# JM24023-Y009-A-V1_0.net
KiCad netlist of a schematic drawn in Altium Designer
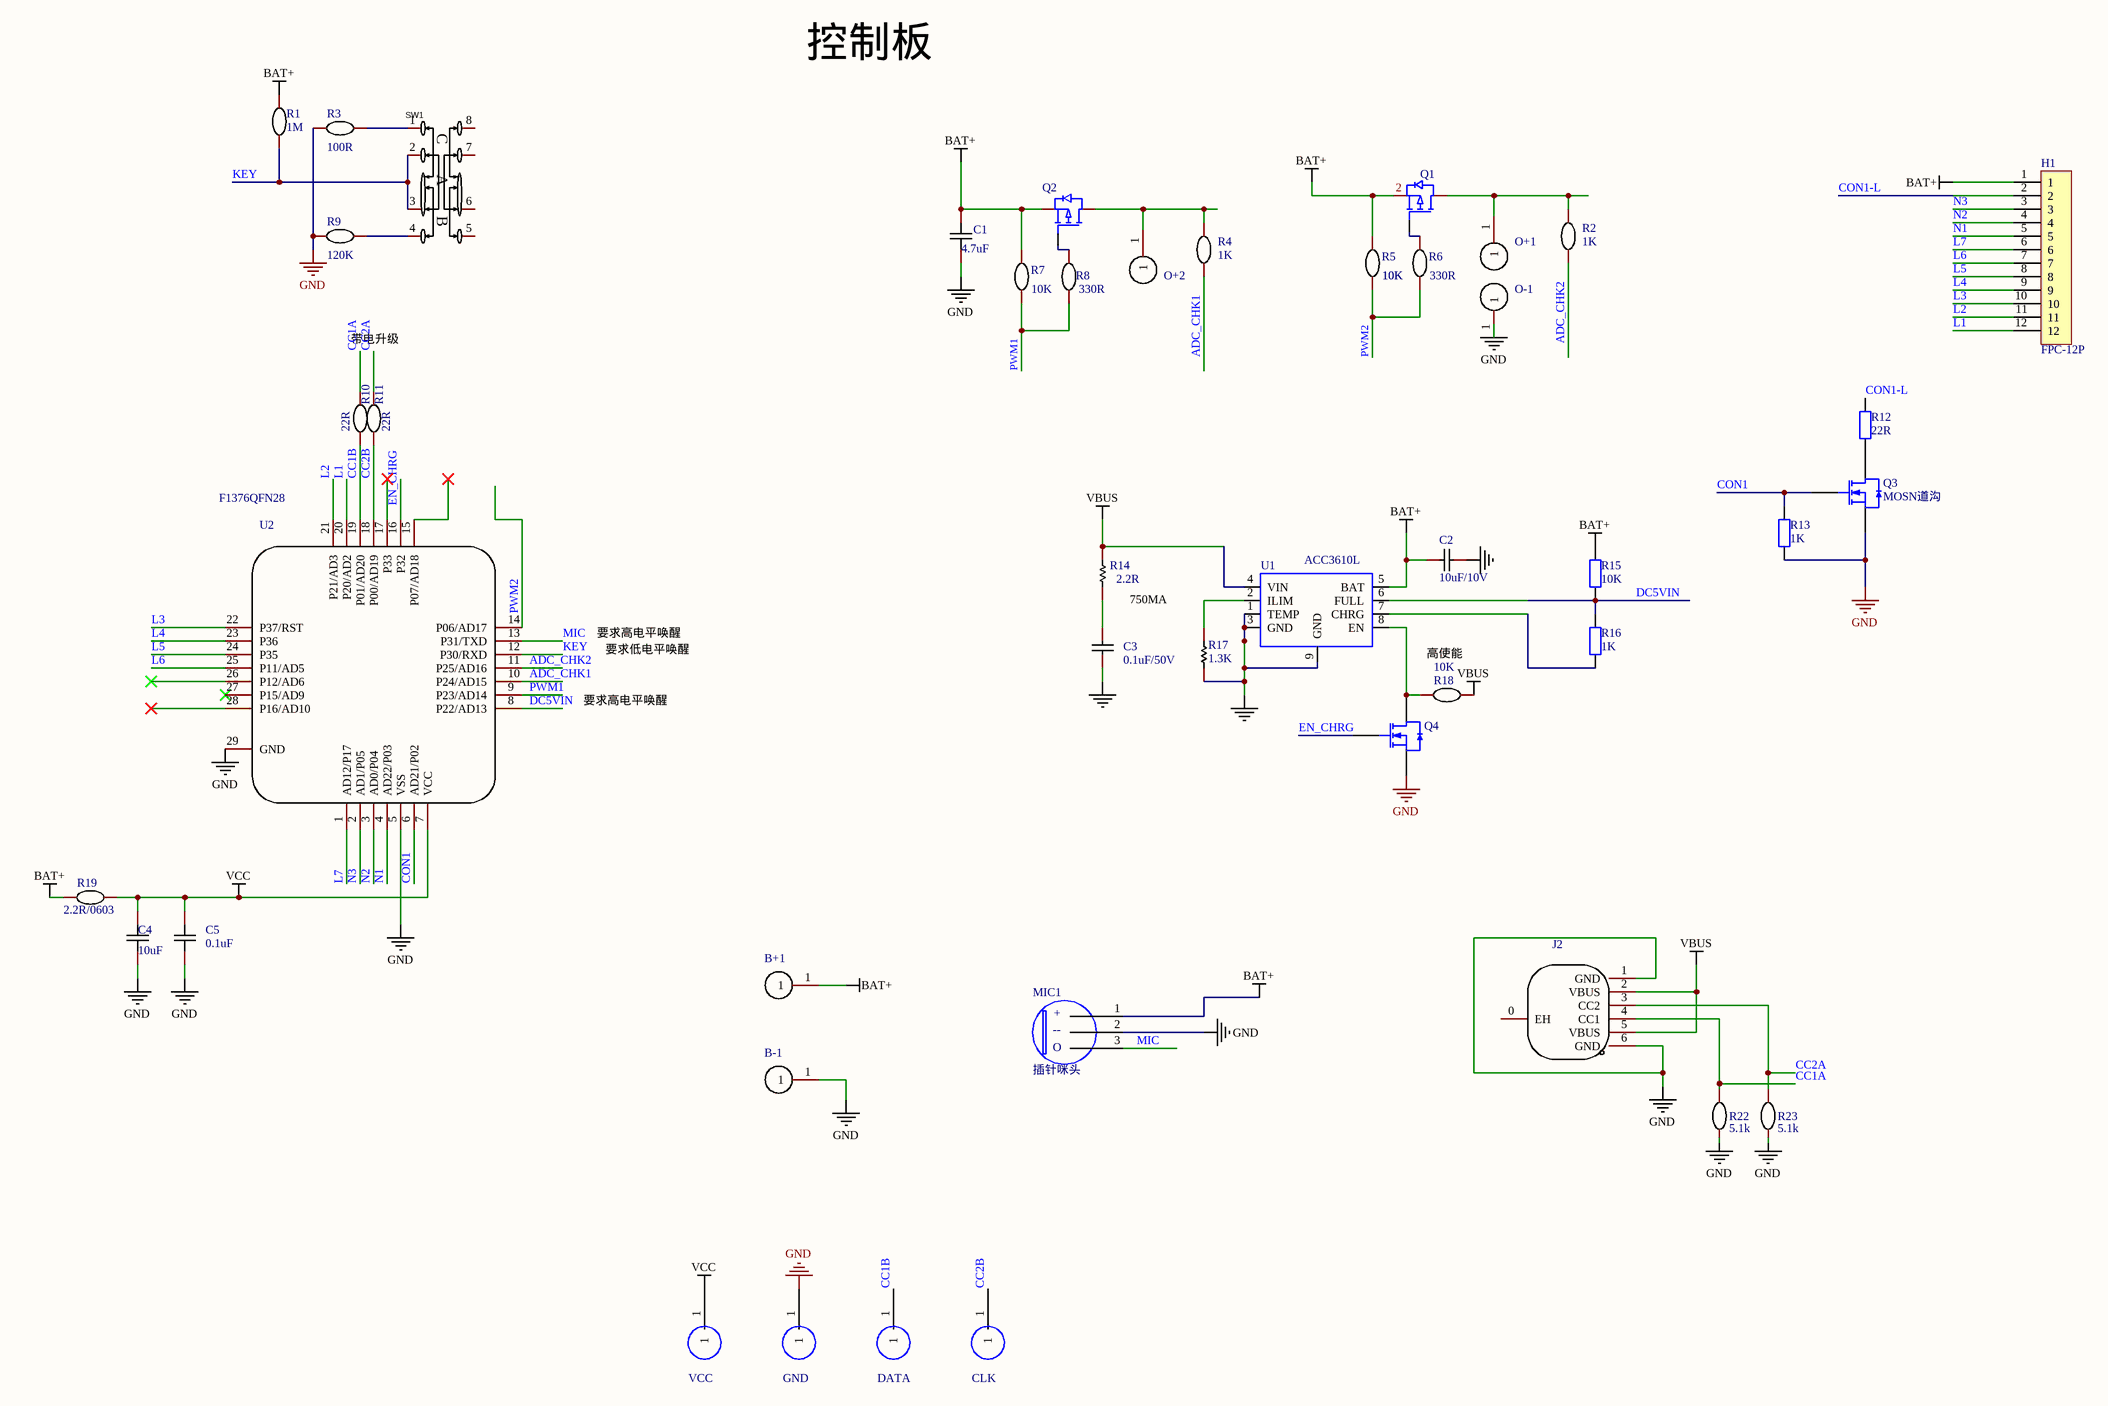
[diagram p0: JM24023-Y009-A-V1.0.schdoc]

(export (version "E")
  (design (tool "Eeschema 10.0.6"))
  (components
    (comp (ref "B+1")
      (value "电池正")
      (footprint "TP1.5")
      (fields (field (name "MANUFACTURER") "XFCN(兴飞)") (field (name "MANUFACTURER PART") "PZ254V-11-01P"))
      (libsource (lib "altium-import") (part "root_2_电池正_"))
    )
    (comp (ref "B-1")
      (value "电池负")
      (footprint "TP1.5")
      (fields (field (name "MANUFACTURER") "XFCN(兴飞)") (field (name "MANUFACTURER PART") "PZ254V-11-01P"))
      (libsource (lib "altium-import") (part "root_2_电池负_"))
    )
    (comp (ref "C1")
      (value "4.7uF10V")
      (footprint "C0402S")
      (fields (field (name "DEVICE") "4.7uF"))
      (libsource (lib "altium-import") (part "root_1_4.7uF10V_"))
    )
    (comp (ref "C2")
      (value "10uF/10V")
      (footprint "C0402S")
      (libsource (lib "altium-import") (part "root_2_10uF/10V_"))
    )
    (comp (ref "C3")
      (value "0.1uF/50V")
      (footprint "C0402S")
      (fields (field (name "NAME") "0.1uF/50V"))
      (libsource (lib "altium-import") (part "root_1_0.1uF/50V_"))
    )
    (comp (ref "C4")
      (value "10uF")
      (footprint "C0402S")
      (fields (field (name "NAME") "10uF"))
      (libsource (lib "altium-import") (part "root_3_mirrored_10uF_"))
    )
    (comp (ref "C5")
      (value "0.1uF")
      (footprint "C0402S")
      (fields (field (name "NAME") "0.1uF"))
      (libsource (lib "altium-import") (part "root_3_mirrored_0.1uF_"))
    )
    (comp (ref "CLK") (value "PAD-烧入测试") (footprint "TP1.5") (libsource (lib "JM原理图库") (part "PAD-烧入测试")))
    (comp (ref "DATA") (value "PAD-烧入测试") (footprint "TP1.5") (libsource (lib "JM原理图库") (part "PAD-烧入测试")))
    (comp (ref "GND") (value "PAD-烧入测试") (footprint "TP1.5") (libsource (lib "JM原理图库") (part "PAD-烧入测试")))
    (comp (ref "H1")
      (value "FPC-12P")
      (footprint "CONN-SMD_12P-P0.50_L3.1-W8.0")
      (libsource (lib "JM原理图库") (part "FPC-12P"))
    )
    (comp (ref "J2")
      (value "TYPE-C 6P(073)-6.5MM")
      (footprint "USB_TYPEC_6L8 -2.0立贴")
      (fields
        (field (name "MANUFACTURER") "SHOU HAN(首韩)")
        (field (name "MANUFACTURER PART") "TYPE-C 6P(073)")
      )
      (libsource (lib "altium-import") (part "root_2_TYPE-C 6P(073)-6.5MM_"))
    )
    (comp (ref "MIC1") (value "插针咪头") (footprint "三针咪/一芯微") (libsource (lib "JM原理图库") (part "3Lin咪头")))
    (comp (ref "O+1")
      (value "加热丝输出")
      (footprint "TP1.5")
      (fields (field (name "MANUFACTURER") "XFCN(兴飞)") (field (name "MANUFACTURER PART") "PZ254V-11-01P"))
      (libsource (lib "altium-import") (part "root_3_加热丝输出_"))
    )
    (comp (ref "O+2")
      (value "加热丝输出")
      (footprint "TP1.5")
      (fields (field (name "MANUFACTURER") "XFCN(兴飞)") (field (name "MANUFACTURER PART") "PZ254V-11-01P"))
      (libsource (lib "altium-import") (part "root_3_加热丝输出_"))
    )
    (comp (ref "O-1")
      (value "加热丝输出")
      (footprint "TP1.5")
      (fields (field (name "MANUFACTURER") "XFCN(兴飞)") (field (name "MANUFACTURER PART") "PZ254V-11-01P"))
      (libsource (lib "altium-import") (part "root_1_加热丝输出_"))
    )
    (comp (ref "Q1")
      (value "P沟场效应管")
      (footprint "SOT-23-3_L2.9-W1.6-P1.90-LS2.8-BR")
      (description "P-Channel Switch with Low RDS(on),SMD,VDS=-20V VGS=±12V ID-0.66A RDS(on)=7Ω")
      (libsource (lib "") (part "PMOS_1"))
    )
    (comp (ref "Q2")
      (value "P沟场效应管")
      (footprint "SOT-23-3_L2.9-W1.6-P1.90-LS2.8-BR")
      (description "P-Channel Switch with Low RDS(on),SMD,VDS=-20V VGS=±12V ID-0.66A RDS(on)=7Ω")
      (libsource (lib "JM原理图库") (part "PMOS"))
    )
    (comp (ref "Q3")
      (value "MOSN道沟")
      (footprint "SOT-523-3_L1.7-W0.8-P1.00-LS1.5-BR")
      (description "MOS(场效应管)")
      (libsource (lib "JM原理图库") (part "MOSN道沟"))
    )
    (comp (ref "Q4")
      (value "~")
      (footprint "SOT-523-3_L1.7-W0.8-P1.00-LS1.5-BR")
      (description "MOS(场效应管)")
      (libsource (lib "JM原理图库") (part "MOSN道沟"))
    )
    (comp (ref "R1")
      (value "1M")
      (footprint "R0402S")
      (fields (field (name "NAME") "1M"))
      (libsource (lib "altium-import") (part "root_1_47K_"))
    )
    (comp (ref "R2")
      (value "1K")
      (footprint "R0402S")
      (fields (field (name "NAME") "1K"))
      (libsource (lib "altium-import") (part "root_3_1K_"))
    )
    (comp (ref "R3")
      (value "100R")
      (footprint "R0402S")
      (libsource (lib "altium-import") (part "root_2_47K_"))
    )
    (comp (ref "R4")
      (value "1K")
      (footprint "R0402S")
      (fields (field (name "NAME") "1K"))
      (libsource (lib "altium-import") (part "root_3_1K_"))
    )
    (comp (ref "R5")
      (value "10K")
      (footprint "R0402S")
      (fields (field (name "NAME") "10K") (field (name "DEVICE") "10K"))
      (libsource (lib "altium-import") (part "root_1_10K_"))
    )
    (comp (ref "R6")
      (value "330R")
      (footprint "R0402S")
      (fields (field (name "NAME") "330R"))
      (libsource (lib "altium-import") (part "root_1_330R_"))
    )
    (comp (ref "R7")
      (value "10K")
      (footprint "R0402S")
      (fields (field (name "DEVICE") "10K"))
      (libsource (lib "altium-import") (part "root_1_10K_"))
    )
    (comp (ref "R8")
      (value "330R")
      (footprint "R0402S")
      (fields (field (name "DEVICE") "330R"))
      (libsource (lib "altium-import") (part "root_1_330R_"))
    )
    (comp (ref "R9")
      (value "120K")
      (footprint "R0402S")
      (libsource (lib "altium-import") (part "root_2_47K_"))
    )
    (comp (ref "R10")
      (value "22R")
      (footprint "R0402S")
      (libsource (lib "altium-import") (part "root_3_22R_"))
    )
    (comp (ref "R11")
      (value "22R")
      (footprint "R0402S")
      (libsource (lib "altium-import") (part "root_3_22R_"))
    )
    (comp (ref "R12")
      (value "22R")
      (footprint "R0402S")
      (description "贴片电阻")
      (libsource (lib "JM原理图库") (part "RES 1%"))
    )
    (comp (ref "R13")
      (value "1K")
      (footprint "R0402S")
      (description "贴片电阻")
      (libsource (lib "JM原理图库") (part "RES 1%"))
    )
    (comp (ref "R14")
      (value "2.2R")
      (footprint "R0402S")
      (fields (field (name "NAME") "2.2R"))
      (libsource (lib "altium-import") (part "root_1_2R2/0402_"))
    )
    (comp (ref "R15")
      (value "10K")
      (footprint "R0402S")
      (description "贴片电阻")
      (libsource (lib "") (part "RES 1%_1"))
    )
    (comp (ref "R16")
      (value "1K")
      (footprint "R0402S")
      (description "贴片电阻")
      (libsource (lib "") (part "RES 1%_1"))
    )
    (comp (ref "R17")
      (value "1.3K")
      (footprint "R0402S")
      (fields (field (name "DEVICE") "1.3K"))
      (libsource (lib "altium-import") (part "root_3_1.3K_"))
    )
    (comp (ref "R18")
      (value "10k")
      (footprint "R0402S")
      (description "电阻类型:厚膜电阻;阻值:10kΩ;精度:±1%;功率:62.5mW;最大工作电压:50V;温度系数:±100ppm/℃;")
      (fields
        (field (name "SYMBOL") "10K")
        (field (name "MANUFACTURER") "YAGEO(国巨)")
        (field (name "MANUFACTURER PART") "RC0402FR-0710KL")
      )
      (libsource (lib "altium-import") (part "root_2_RC0402FR-0710KL_"))
    )
    (comp (ref "R19")
      (value "2.2R/0603")
      (footprint "R0603S")
      (libsource (lib "altium-import") (part "root_0_2.2R/0805_"))
    )
    (comp (ref "R22")
      (value "5.1k")
      (footprint "R0402S")
      (fields (field (name "NAME") "5.1k"))
      (libsource (lib "altium-import") (part "root_1_5.1k_"))
    )
    (comp (ref "R23")
      (value "5.1k")
      (footprint "R0402S")
      (fields (field (name "NAME") "5.1k"))
      (libsource (lib "altium-import") (part "root_1_5.1k_"))
    )
    (comp (ref "SW1")
      (value "SW1")
      (footprint "SW-SMD_8P-L9.9-W3.5-P2.00")
      (fields (field (name "MANUFACTURER") "Yuandi(元迪)") (field (name "MANUFACTURER PART") "TA-3537S-A1"))
      (libsource (lib "JM原理图库") (part "8脚3档拨动开关"))
    )
    (comp (ref "U1")
      (value "ACC3610L")
      (footprint "DFN-8-2X2-P0.50-TL-EP1.6")
      (description "36V 集成 OVP 保护 1.0A 锂电池线性充电芯片")
      (libsource (lib "JM原理图库") (part "SA4356"))
    )
    (comp (ref "U2")
      (value "F1376QFN28")
      (footprint "QFN-28_L4.0-W4.0-P0.40-BL-EP2.6")
      (libsource (lib "altium-import") (part "root_0_F1376QFN28_"))
    )
    (comp (ref "VCC") (value "PAD-烧入测试") (footprint "TP1.5") (libsource (lib "JM原理图库") (part "PAD-烧入测试")))
  )
  (nets
    (net (code "1") (name "/ADC_CHK1") (class "Default")
      (node (ref "R4") (pin "2") (pinfunction "2_2") (pintype "passive"))
      (node (ref "U2") (pin "10") (pinfunction "P24/AD15_10") (pintype "passive"))
    )
    (net (code "2") (name "/ADC_CHK2") (class "Default")
      (node (ref "R2") (pin "2") (pinfunction "2_2") (pintype "passive"))
      (node (ref "U2") (pin "11") (pinfunction "P25/AD16_11") (pintype "passive"))
    )
    (net (code "3") (name "/CC1A") (class "Default")
      (node (ref "J2") (pin "4") (pinfunction "CC1_4") (pintype "passive"))
      (node (ref "R10") (pin "1") (pinfunction "1_1") (pintype "passive"))
      (node (ref "R22") (pin "2") (pinfunction "2_2") (pintype "passive"))
    )
    (net (code "4") (name "/CC1B") (class "Default")
      (node (ref "DATA") (pin "1") (pinfunction "1_1") (pintype "passive"))
      (node (ref "R10") (pin "2") (pinfunction "2_2") (pintype "passive"))
      (node (ref "U2") (pin "19") (pinfunction "P01/AD20_19") (pintype "passive"))
    )
    (net (code "5") (name "/CC2A") (class "Default")
      (node (ref "J2") (pin "3") (pinfunction "CC2_3") (pintype "passive"))
      (node (ref "R11") (pin "1") (pinfunction "1_1") (pintype "passive"))
      (node (ref "R23") (pin "2") (pinfunction "2_2") (pintype "passive"))
    )
    (net (code "6") (name "/CC2B") (class "Default")
      (node (ref "CLK") (pin "1") (pinfunction "1_1") (pintype "passive"))
      (node (ref "R11") (pin "2") (pinfunction "2_2") (pintype "passive"))
      (node (ref "U2") (pin "18") (pinfunction "P00/AD19_18") (pintype "passive"))
    )
    (net (code "7") (name "/CON1") (class "Default")
      (node (ref "Q3") (pin "1") (pinfunction "G_1") (pintype "passive"))
      (node (ref "R13") (pin "1") (pinfunction "1_1") (pintype "passive"))
      (node (ref "U2") (pin "6") (pinfunction "AD21/P02_6") (pintype "passive"))
    )
    (net (code "8") (name "/CON1-L") (class "Default")
      (node (ref "H1") (pin "2") (pinfunction "2_2") (pintype "passive"))
      (node (ref "R12") (pin "1") (pinfunction "1_1") (pintype "passive"))
    )
    (net (code "9") (name "/DC5VIN") (class "Default")
      (node (ref "R15") (pin "1") (pinfunction "1_1") (pintype "passive"))
      (node (ref "R16") (pin "2") (pinfunction "2_2") (pintype "passive"))
      (node (ref "U1") (pin "6") (pinfunction "FULL_6") (pintype "passive"))
      (node (ref "U2") (pin "8") (pinfunction "P22/AD13_8") (pintype "passive"))
    )
    (net (code "10") (name "/EN_CHRG") (class "Default")
      (node (ref "Q4") (pin "1") (pinfunction "G_1") (pintype "passive"))
      (node (ref "U2") (pin "16") (pinfunction "P32_16") (pintype "passive"))
    )
    (net (code "11") (name "/KEY") (class "Default")
      (node (ref "R1") (pin "1") (pinfunction "1_1") (pintype "passive"))
      (node (ref "SW1") (pin "2") (pinfunction "2_2") (pintype "passive"))
      (node (ref "SW1") (pin "3") (pinfunction "3_3") (pintype "passive"))
      (node (ref "U2") (pin "12") (pinfunction "P30/RXD_12") (pintype "passive"))
    )
    (net (code "12") (name "/L1") (class "Default")
      (node (ref "H1") (pin "12") (pinfunction "12_12") (pintype "passive"))
      (node (ref "U2") (pin "20") (pinfunction "P20/AD2_20") (pintype "passive"))
    )
    (net (code "13") (name "/L2") (class "Default")
      (node (ref "H1") (pin "11") (pinfunction "11_11") (pintype "passive"))
      (node (ref "U2") (pin "21") (pinfunction "P21/AD3_21") (pintype "passive"))
    )
    (net (code "14") (name "/L3") (class "Default")
      (node (ref "H1") (pin "10") (pinfunction "10_10") (pintype "passive"))
      (node (ref "U2") (pin "22") (pinfunction "P37/RST_22") (pintype "passive"))
    )
    (net (code "15") (name "/L4") (class "Default")
      (node (ref "H1") (pin "9") (pinfunction "9_9") (pintype "passive"))
      (node (ref "U2") (pin "23") (pinfunction "P36_23") (pintype "passive"))
    )
    (net (code "16") (name "/L5") (class "Default")
      (node (ref "H1") (pin "8") (pinfunction "8_8") (pintype "passive"))
      (node (ref "U2") (pin "24") (pinfunction "P35_24") (pintype "passive"))
    )
    (net (code "17") (name "/L6") (class "Default")
      (node (ref "H1") (pin "7") (pinfunction "7_7") (pintype "passive"))
      (node (ref "U2") (pin "25") (pinfunction "P11/AD5_25") (pintype "passive"))
    )
    (net (code "18") (name "/L7") (class "Default")
      (node (ref "H1") (pin "6") (pinfunction "6_6") (pintype "passive"))
      (node (ref "U2") (pin "1") (pinfunction "AD12/P17_1") (pintype "passive"))
    )
    (net (code "19") (name "/MIC") (class "Default")
      (node (ref "MIC1") (pin "3") (pinfunction "OUT_3") (pintype "passive"))
      (node (ref "U2") (pin "13") (pinfunction "P31/TXD_13") (pintype "passive"))
    )
    (net (code "20") (name "/N1") (class "Default")
      (node (ref "H1") (pin "5") (pinfunction "5_5") (pintype "passive"))
      (node (ref "U2") (pin "4") (pinfunction "AD22/P03_4") (pintype "passive"))
    )
    (net (code "21") (name "/N2") (class "Default")
      (node (ref "H1") (pin "4") (pinfunction "4_4") (pintype "passive"))
      (node (ref "U2") (pin "3") (pinfunction "AD0/P04_3") (pintype "passive"))
    )
    (net (code "22") (name "/N3") (class "Default")
      (node (ref "H1") (pin "3") (pinfunction "3_3") (pintype "passive"))
      (node (ref "U2") (pin "2") (pinfunction "AD1/P05_2") (pintype "passive"))
    )
    (net (code "23") (name "/PWM1") (class "Default")
      (node (ref "R7") (pin "1") (pinfunction "1_1") (pintype "passive"))
      (node (ref "R8") (pin "1") (pinfunction "1_1") (pintype "passive"))
      (node (ref "U2") (pin "9") (pinfunction "P23/AD14_9") (pintype "passive"))
    )
    (net (code "24") (name "/PWM2") (class "Default")
      (node (ref "R5") (pin "1") (pinfunction "1_1") (pintype "passive"))
      (node (ref "R6") (pin "1") (pinfunction "1_1") (pintype "passive"))
      (node (ref "U2") (pin "14") (pinfunction "P06/AD17_14") (pintype "passive"))
    )
    (net (code "25") (name "BAT+") (class "Default")
      (node (ref "B+1") (pin "1") (pinfunction "1_1") (pintype "passive"))
      (node (ref "C1") (pin "2") (pinfunction "2_2") (pintype "passive"))
      (node (ref "C2") (pin "2") (pinfunction "2_2") (pintype "passive"))
      (node (ref "H1") (pin "1") (pinfunction "1_1") (pintype "passive"))
      (node (ref "MIC1") (pin "1") (pinfunction "M+_1") (pintype "passive"))
      (node (ref "Q1") (pin "2") (pinfunction "S_2") (pintype "passive"))
      (node (ref "Q2") (pin "2") (pinfunction "S_2") (pintype "passive"))
      (node (ref "R1") (pin "2") (pinfunction "2_2") (pintype "passive"))
      (node (ref "R15") (pin "2") (pinfunction "2_2") (pintype "passive"))
      (node (ref "R19") (pin "1") (pinfunction "1_1") (pintype "passive"))
      (node (ref "R5") (pin "2") (pinfunction "2_2") (pintype "passive"))
      (node (ref "R7") (pin "2") (pinfunction "2_2") (pintype "passive"))
      (node (ref "U1") (pin "5") (pinfunction "BAT_5") (pintype "passive"))
    )
    (net (code "26") (name "GND") (class "Default")
      (node (ref "B-1") (pin "1") (pinfunction "1_1") (pintype "passive"))
      (node (ref "C1") (pin "1") (pinfunction "1_1") (pintype "passive"))
      (node (ref "C2") (pin "1") (pinfunction "1_1") (pintype "passive"))
      (node (ref "C3") (pin "1") (pinfunction "1_1") (pintype "passive"))
      (node (ref "C4") (pin "2") (pinfunction "2_2") (pintype "passive"))
      (node (ref "C5") (pin "2") (pinfunction "2_2") (pintype "passive"))
      (node (ref "GND") (pin "1") (pinfunction "1_1") (pintype "passive"))
      (node (ref "J2") (pin "1") (pinfunction "GND_1") (pintype "passive"))
      (node (ref "J2") (pin "6") (pinfunction "GND_6") (pintype "passive"))
      (node (ref "MIC1") (pin "2") (pinfunction "M-_2") (pintype "passive"))
      (node (ref "O-1") (pin "1") (pinfunction "1_1") (pintype "passive"))
      (node (ref "Q3") (pin "2") (pinfunction "S_2") (pintype "passive"))
      (node (ref "Q4") (pin "2") (pinfunction "S_2") (pintype "passive"))
      (node (ref "R13") (pin "2") (pinfunction "2_2") (pintype "passive"))
      (node (ref "R17") (pin "2") (pinfunction "2_2") (pintype "passive"))
      (node (ref "R22") (pin "1") (pinfunction "1_1") (pintype "passive"))
      (node (ref "R23") (pin "1") (pinfunction "1_1") (pintype "passive"))
      (node (ref "R3") (pin "2") (pinfunction "2_2") (pintype "passive"))
      (node (ref "R9") (pin "2") (pinfunction "2_2") (pintype "passive"))
      (node (ref "U1") (pin "1") (pinfunction "TEMP_1") (pintype "passive"))
      (node (ref "U1") (pin "3") (pinfunction "GND_3") (pintype "passive"))
      (node (ref "U1") (pin "9") (pinfunction "GND_9") (pintype "passive"))
      (node (ref "U2") (pin "29") (pinfunction "GND_29") (pintype "passive"))
      (node (ref "U2") (pin "5") (pinfunction "VSS_5") (pintype "passive"))
    )
    (net (code "27") (name "Net-(C3-Pad2)") (class "Default")
      (node (ref "C3") (pin "2") (pinfunction "2_2") (pintype "passive"))
      (node (ref "R14") (pin "1") (pinfunction "1_1") (pintype "passive"))
    )
    (net (code "28") (name "Net-(Q1-D)") (class "Default")
      (node (ref "O+1") (pin "1") (pinfunction "1_1") (pintype "passive"))
      (node (ref "Q1") (pin "3") (pinfunction "D_3") (pintype "passive"))
      (node (ref "R2") (pin "1") (pinfunction "1_1") (pintype "passive"))
    )
    (net (code "29") (name "Net-(Q1-G)") (class "Default")
      (node (ref "Q1") (pin "1") (pinfunction "G_1") (pintype "passive"))
      (node (ref "R6") (pin "2") (pinfunction "2_2") (pintype "passive"))
    )
    (net (code "30") (name "Net-(Q2-D)") (class "Default")
      (node (ref "O+2") (pin "1") (pinfunction "1_1") (pintype "passive"))
      (node (ref "Q2") (pin "3") (pinfunction "D_3") (pintype "passive"))
      (node (ref "R4") (pin "1") (pinfunction "1_1") (pintype "passive"))
    )
    (net (code "31") (name "Net-(Q2-G)") (class "Default")
      (node (ref "Q2") (pin "1") (pinfunction "G_1") (pintype "passive"))
      (node (ref "R8") (pin "2") (pinfunction "2_2") (pintype "passive"))
    )
    (net (code "32") (name "Net-(Q3-D)") (class "Default")
      (node (ref "Q3") (pin "3") (pinfunction "D_3") (pintype "passive"))
      (node (ref "R12") (pin "2") (pinfunction "2_2") (pintype "passive"))
    )
    (net (code "33") (name "Net-(Q4-D)") (class "Default")
      (node (ref "Q4") (pin "3") (pinfunction "D_3") (pintype "passive"))
      (node (ref "R18") (pin "2") (pinfunction "2_2") (pintype "passive"))
      (node (ref "U1") (pin "8") (pinfunction "EN_8") (pintype "passive"))
    )
    (net (code "34") (name "Net-(R3-Pad1)") (class "Default")
      (node (ref "R3") (pin "1") (pinfunction "1_1") (pintype "passive"))
      (node (ref "SW1") (pin "1") (pinfunction "1_1") (pintype "passive"))
    )
    (net (code "35") (name "Net-(R9-Pad1)") (class "Default")
      (node (ref "R9") (pin "1") (pinfunction "1_1") (pintype "passive"))
      (node (ref "SW1") (pin "4") (pinfunction "4_4") (pintype "passive"))
    )
    (net (code "36") (name "Net-(U1-CHRG)") (class "Default")
      (node (ref "R16") (pin "1") (pinfunction "1_1") (pintype "passive"))
      (node (ref "U1") (pin "7") (pinfunction "CHRG_7") (pintype "passive"))
    )
    (net (code "37") (name "Net-(U1-ILIM)") (class "Default")
      (node (ref "R17") (pin "1") (pinfunction "1_1") (pintype "passive"))
      (node (ref "U1") (pin "2") (pinfunction "ILIM_2") (pintype "passive"))
    )
    (net (code "38") (name "VBUS") (class "Default")
      (node (ref "J2") (pin "2") (pinfunction "VBUS_2") (pintype "passive"))
      (node (ref "J2") (pin "5") (pinfunction "VBUS_5") (pintype "passive"))
      (node (ref "R14") (pin "2") (pinfunction "2_2") (pintype "passive"))
      (node (ref "R18") (pin "1") (pinfunction "1_1") (pintype "passive"))
      (node (ref "U1") (pin "4") (pinfunction "VIN_4") (pintype "passive"))
    )
    (net (code "39") (name "VCC") (class "Default")
      (node (ref "C4") (pin "1") (pinfunction "1_1") (pintype "passive"))
      (node (ref "C5") (pin "1") (pinfunction "1_1") (pintype "passive"))
      (node (ref "R19") (pin "2") (pinfunction "2_2") (pintype "passive"))
      (node (ref "U2") (pin "7") (pinfunction "VCC_7") (pintype "passive"))
      (node (ref "VCC") (pin "1") (pinfunction "1_1") (pintype "passive"))
    )
    (net (code "40") (name "unconnected-(J2-EH-Pad0)") (class "Default")
      (node (ref "J2") (pin "0") (pinfunction "EH_0") (pintype "passive"))
    )
    (net (code "41") (name "unconnected-(SW1-Pad5)") (class "Default")
      (node (ref "SW1") (pin "5") (pinfunction "5_5") (pintype "passive"))
    )
    (net (code "42") (name "unconnected-(SW1-Pad6)") (class "Default")
      (node (ref "SW1") (pin "6") (pinfunction "6_6") (pintype "passive"))
    )
    (net (code "43") (name "unconnected-(SW1-Pad7)") (class "Default")
      (node (ref "SW1") (pin "7") (pinfunction "7_7") (pintype "passive"))
    )
    (net (code "44") (name "unconnected-(SW1-Pad8)") (class "Default")
      (node (ref "SW1") (pin "8") (pinfunction "8_8") (pintype "passive"))
    )
    (net (code "45") (name "unconnected-(U2-P07{slash}AD18-Pad15)") (class "Default")
      (node (ref "U2") (pin "15") (pinfunction "P07/AD18_15") (pintype "passive+no_connect"))
    )
    (net (code "46") (name "unconnected-(U2-P12{slash}AD6-Pad26)") (class "Default")
      (node (ref "U2") (pin "26") (pinfunction "P12/AD6_26") (pintype "passive+no_connect"))
    )
    (net (code "47") (name "unconnected-(U2-P15{slash}AD9-Pad27)") (class "Default")
      (node (ref "U2") (pin "27") (pinfunction "P15/AD9_27") (pintype "passive+no_connect"))
    )
    (net (code "48") (name "unconnected-(U2-P16{slash}AD10-Pad28)") (class "Default")
      (node (ref "U2") (pin "28") (pinfunction "P16/AD10_28") (pintype "passive+no_connect"))
    )
    (net (code "49") (name "unconnected-(U2-P33-Pad17)") (class "Default")
      (node (ref "U2") (pin "17") (pinfunction "P33_17") (pintype "passive+no_connect"))
    )
  )
)
